# MCU.net
KiCad netlist of a schematic drawn in Altium Designer
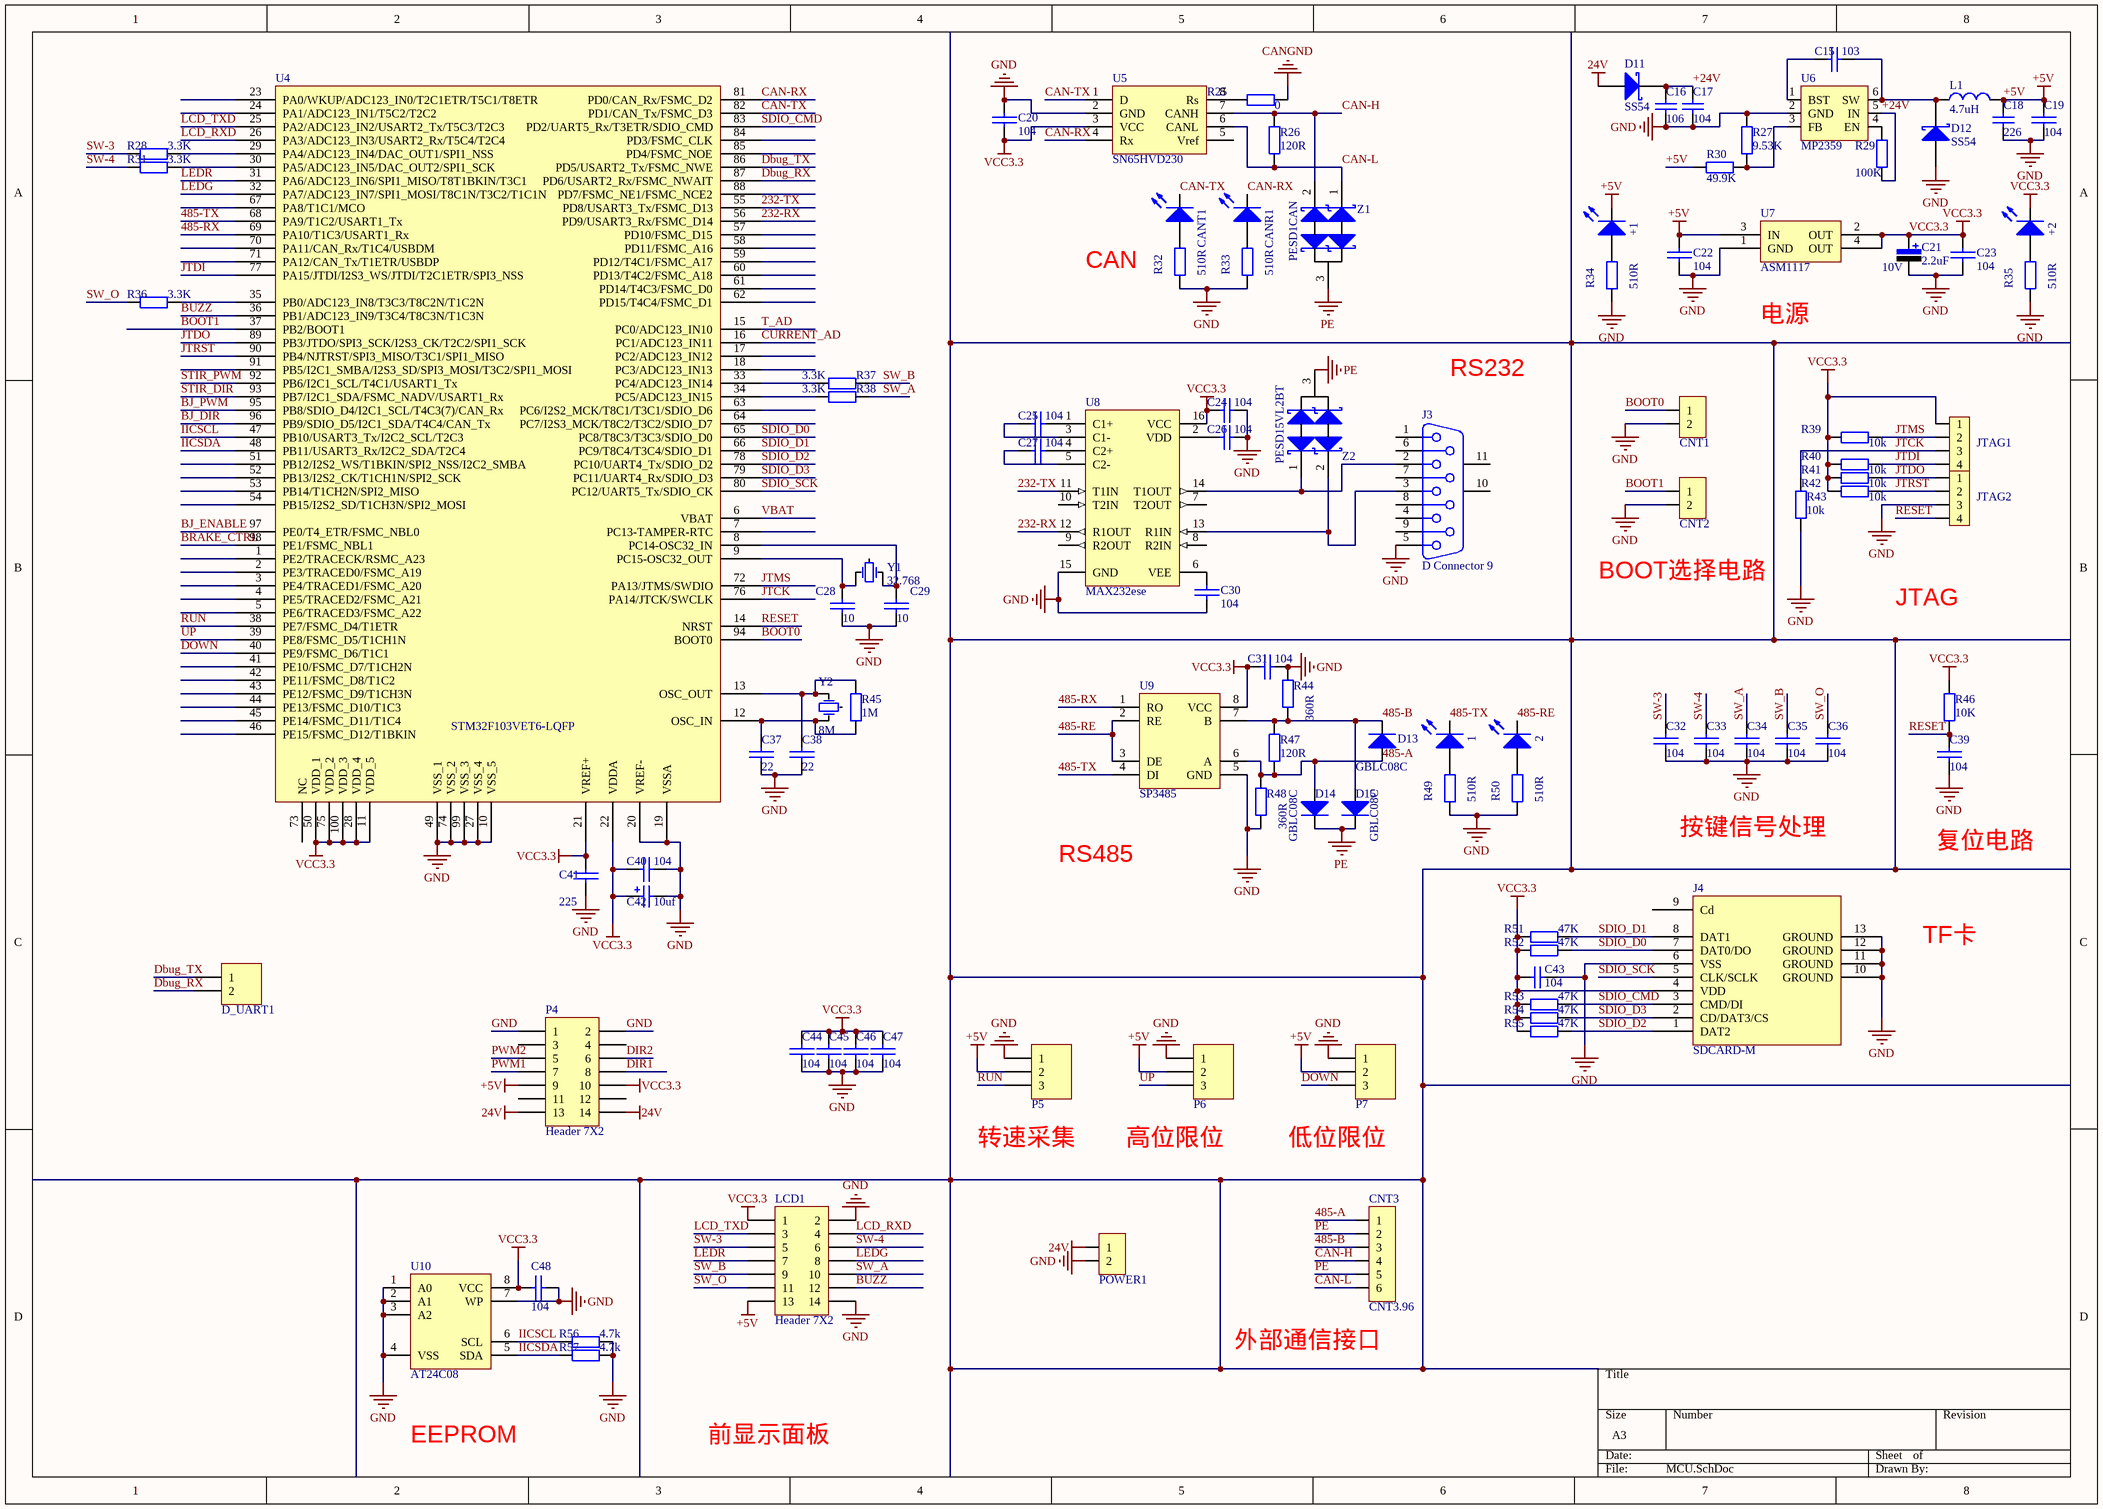
[diagram p0: MCU.SchDoc]

(export (version "E")
  (design (tool "Eeschema 10.0.6"))
  (components
    (comp (ref "+1") (value "COLOUR") (footprint "0603LED") (libsource (lib "MY_Library") (part "ledφ6")))
    (comp (ref "+2") (value "COLOUR") (footprint "0603LED") (libsource (lib "MY_Library") (part "ledφ6")))
    (comp (ref "1") (value "COLOUR") (footprint "0603LED") (libsource (lib "MY_Library") (part "ledφ6")))
    (comp (ref "2") (value "COLOUR") (footprint "0603LED") (libsource (lib "MY_Library") (part "ledφ6")))
    (comp (ref "C15")
      (value "103")
      (footprint "0603C")
      (description "安规电容")
      (libsource (lib "MY_Library") (part "CAP X"))
    )
    (comp (ref "C16")
      (value "1210")
      (footprint "1210")
      (description "无极性电容")
      (fields (field (name "容量") "106") (field (name "PUBLISHER") "Altium Limited"))
      (libsource (lib "altium-import") (part "root_1_Cap_"))
    )
    (comp (ref "C17")
      (value "104")
      (footprint "0603-2")
      (description "无极性电容")
      (fields (field (name "Comment") "Cap") (field (name "PUBLISHER") "Altium Limited"))
      (libsource (lib "Fszhang") (part "Cap"))
    )
    (comp (ref "C18")
      (value "226")
      (footprint "1206")
      (description "无极性电容")
      (fields (field (name "Comment") "Cap") (field (name "PUBLISHER") "Altium Limited"))
      (libsource (lib "Fszhang") (part "Cap"))
    )
    (comp (ref "C19")
      (value "104")
      (footprint "0603C")
      (description "安规电容")
      (libsource (lib "MY_Library") (part "CAP X"))
    )
    (comp (ref "C20")
      (value "104")
      (footprint "0603C")
      (description "安规电容")
      (libsource (lib "MY_Library") (part "CAP X"))
    )
    (comp (ref "C21")
      (value "2.2uF")
      (footprint "CAP-3216")
      (description "极性电解电容")
      (fields
        (field (name "VOL") "10V")
        (field (name "Comment") "Cap Pol")
        (field (name "PUBLISHER") "Altium Limited")
      )
      (libsource (lib "Fszhang") (part "Cap Pol"))
    )
    (comp (ref "C22")
      (value "104")
      (footprint "0603C")
      (description "安规电容")
      (libsource (lib "MY_Library") (part "CAP X"))
    )
    (comp (ref "C23")
      (value "104")
      (footprint "0603C")
      (description "安规电容")
      (libsource (lib "MY_Library") (part "CAP X"))
    )
    (comp (ref "C24")
      (value "104")
      (footprint "0603C")
      (description "安规电容")
      (libsource (lib "MY_Library") (part "CAP X"))
    )
    (comp (ref "C25")
      (value "104")
      (footprint "0603C")
      (description "安规电容")
      (libsource (lib "MY_Library") (part "CAP X"))
    )
    (comp (ref "C26")
      (value "104")
      (footprint "0603C")
      (description "安规电容")
      (libsource (lib "MY_Library") (part "CAP X"))
    )
    (comp (ref "C27")
      (value "104")
      (footprint "0603C")
      (description "安规电容")
      (libsource (lib "MY_Library") (part "CAP X"))
    )
    (comp (ref "C28")
      (value "10")
      (footprint "0603C")
      (description "安规电容")
      (libsource (lib "MY_Library") (part "CAP X"))
    )
    (comp (ref "C29")
      (value "10")
      (footprint "0603C")
      (description "安规电容")
      (libsource (lib "MY_Library") (part "CAP X"))
    )
    (comp (ref "C30")
      (value "104")
      (footprint "0603C")
      (description "安规电容")
      (libsource (lib "MY_Library") (part "CAP X"))
    )
    (comp (ref "C31")
      (value "104")
      (footprint "0603C")
      (description "安规电容")
      (libsource (lib "MY_Library") (part "CAP X"))
    )
    (comp (ref "C32")
      (value "104")
      (footprint "0603C")
      (description "安规电容")
      (libsource (lib "MY_Library") (part "CAP X"))
    )
    (comp (ref "C33")
      (value "104")
      (footprint "0603C")
      (description "安规电容")
      (libsource (lib "MY_Library") (part "CAP X"))
    )
    (comp (ref "C34")
      (value "104")
      (footprint "0603C")
      (description "安规电容")
      (libsource (lib "MY_Library") (part "CAP X"))
    )
    (comp (ref "C35")
      (value "104")
      (footprint "0603C")
      (description "安规电容")
      (libsource (lib "MY_Library") (part "CAP X"))
    )
    (comp (ref "C36")
      (value "104")
      (footprint "0603C")
      (description "安规电容")
      (libsource (lib "MY_Library") (part "CAP X"))
    )
    (comp (ref "C37")
      (value "22")
      (footprint "0603C")
      (description "安规电容")
      (libsource (lib "MY_Library") (part "CAP X"))
    )
    (comp (ref "C38")
      (value "22")
      (footprint "0603C")
      (description "安规电容")
      (libsource (lib "MY_Library") (part "CAP X"))
    )
    (comp (ref "C39")
      (value "104")
      (footprint "0603C")
      (description "安规电容")
      (libsource (lib "MY_Library") (part "CAP X"))
    )
    (comp (ref "C40")
      (value "104")
      (footprint "0603C")
      (description "安规电容")
      (libsource (lib "MY_Library") (part "CAP X"))
    )
    (comp (ref "C41")
      (value "225")
      (footprint "0603C")
      (description "安规电容")
      (libsource (lib "MY_Library") (part "CAP X"))
    )
    (comp (ref "C42")
      (value "10uf")
      (footprint "ct3216-18")
      (description "电解电容")
      (libsource (lib "MY_Library") (part "CAP"))
    )
    (comp (ref "C43")
      (value "104")
      (footprint "C-RAD-0603")
      (description "无极性电容")
      (fields (field (name "Comment") "Cap") (field (name "PUBLISHER") "Altium Limited"))
      (libsource (lib "Fszhang") (part "Cap"))
    )
    (comp (ref "C44")
      (value "104")
      (footprint "0603C")
      (description "安规电容")
      (libsource (lib "MY_Library") (part "CAP X"))
    )
    (comp (ref "C45")
      (value "104")
      (footprint "0603C")
      (description "安规电容")
      (libsource (lib "MY_Library") (part "CAP X"))
    )
    (comp (ref "C46")
      (value "104")
      (footprint "0603C")
      (description "安规电容")
      (libsource (lib "MY_Library") (part "CAP X"))
    )
    (comp (ref "C47")
      (value "104")
      (footprint "0603C")
      (description "安规电容")
      (libsource (lib "MY_Library") (part "CAP X"))
    )
    (comp (ref "C48")
      (value "104")
      (footprint "0603C")
      (description "安规电容")
      (libsource (lib "MY_Library") (part "CAP X"))
    )
    (comp (ref "CANR1") (value "COLOUR") (footprint "0603LED") (libsource (lib "MY_Library") (part "ledφ6")))
    (comp (ref "CANT1") (value "COLOUR") (footprint "0603LED") (libsource (lib "MY_Library") (part "ledφ6")))
    (comp (ref "CNT1") (value "cnt2p") (footprint "cont-1") (libsource (lib "MY_Library") (part "cnt2p")))
    (comp (ref "CNT2") (value "cnt2p") (footprint "cont-1") (libsource (lib "MY_Library") (part "cnt2p")))
    (comp (ref "CNT3")
      (value "CNT3.96")
      (footprint "CNT3.96")
      (description "接线端子(3.96MM)")
      (libsource (lib "MY_Library") (part "CNT3.96"))
    )
    (comp (ref "D11")
      (value "D-Schottky")
      (footprint "DIODE-SMA")
      (description "肖特基二极管")
      (fields (field (name "TYPE") "SS54") (field (name "PUBLISHER") "Altium Limited"))
      (libsource (lib "Fszhang") (part "D-Schottky"))
    )
    (comp (ref "D12")
      (value "D-Schottky")
      (footprint "DIODE-SMA")
      (description "肖特基二极管")
      (fields (field (name "TYPE") "SS54") (field (name "PUBLISHER") "Altium Limited"))
      (libsource (lib "Fszhang") (part "D-Schottky"))
    )
    (comp (ref "D13")
      (value "TVS")
      (footprint "DIODE-1206")
      (description "TVS保护")
      (fields (field (name "TYPE") "GBLC08C") (field (name "PUBLISHER") "Altium Limited"))
      (libsource (lib "Fszhang") (part "TVS"))
    )
    (comp (ref "D14")
      (value "TVS")
      (footprint "DIODE-1206")
      (description "TVS保护")
      (fields (field (name "TYPE") "GBLC08C") (field (name "PUBLISHER") "Altium Limited"))
      (libsource (lib "Fszhang") (part "TVS"))
    )
    (comp (ref "D15")
      (value "TVS")
      (footprint "DIODE-1206")
      (description "TVS保护")
      (fields (field (name "TYPE") "GBLC08C") (field (name "PUBLISHER") "Altium Limited"))
      (libsource (lib "Fszhang") (part "TVS"))
    )
    (comp (ref "D_UART1")
      (value "Header 2")
      (footprint "HDR2X1_A")
      (description "接插件")
      (fields (field (name "PUBLISHER") "Altium Limited"))
      (libsource (lib "Fszhang") (part "Header 2"))
    )
    (comp (ref "J3")
      (value "D Connector 9")
      (footprint "DB9-F")
      (description "串口")
      (fields (field (name "PUBLISHER") "Altium Limited"))
      (libsource (lib "Fszhang") (part "D Connector 9"))
    )
    (comp (ref "J4")
      (value "SDCARD-M")
      (footprint "SDCARD-M")
      (description "TF卡槽")
      (libsource (lib "Fszhang") (part "SDCARD-M"))
    )
    (comp (ref "JTAG1")
      (value "单排插针11mm4p")
      (footprint "单排插针2.54")
      (libsource (lib "MY_Library") (part "单排插针11mm4p"))
    )
    (comp (ref "JTAG2")
      (value "单排插针11mm4p")
      (footprint "单排插针2.54")
      (libsource (lib "MY_Library") (part "单排插针11mm4p"))
    )
    (comp (ref "L1")
      (value "4.7uH")
      (footprint "L-SMD-7")
      (description "电感")
      (fields (field (name "Comment") "Inductor") (field (name "PUBLISHER") "Altium Limited"))
      (libsource (lib "Fszhang") (part "Inductor"))
    )
    (comp (ref "LCD1")
      (value "Header 7X2")
      (footprint "HDR7X2_A1")
      (description "Header, 7-Pin")
      (fields (field (name "PUBLISHER") "Altium Limited"))
      (libsource (lib "Fszhang") (part "Header 7X2"))
    )
    (comp (ref "P4")
      (value "Header 7X2")
      (footprint "HDR7X2_A1")
      (description "Header, 7-Pin")
      (fields (field (name "PUBLISHER") "Altium Limited"))
      (libsource (lib "Fszhang") (part "Header 7X2"))
    )
    (comp (ref "P5")
      (value "Header 3")
      (footprint "XH2.54*3卧贴")
      (description "接插件")
      (fields (field (name "PUBLISHER") "Altium Limited"))
      (libsource (lib "Fszhang") (part "Header 3"))
    )
    (comp (ref "P6")
      (value "Header 3")
      (footprint "XH2.54*3卧贴")
      (description "接插件")
      (fields (field (name "PUBLISHER") "Altium Limited"))
      (libsource (lib "Fszhang") (part "Header 3"))
    )
    (comp (ref "P7")
      (value "Header 3")
      (footprint "XH2.54*3卧贴")
      (description "接插件")
      (fields (field (name "PUBLISHER") "Altium Limited"))
      (libsource (lib "Fszhang") (part "Header 3"))
    )
    (comp (ref "POWER1")
      (value "CNT5.08MM*2 WAN")
      (footprint "CNT5.08*2WAN")
      (libsource (lib "MY_Library") (part "CNT5.08MM*2 WAN"))
    )
    (comp (ref "R25")
      (value "0")
      (footprint "0603-1")
      (description "贴片电阻")
      (fields (field (name "Comment") "Res1") (field (name "PUBLISHER") "Altium Limited"))
      (libsource (lib "") (part "Res1_1"))
    )
    (comp (ref "R26")
      (value "120R")
      (footprint "0603-1")
      (description "贴片电阻")
      (fields (field (name "Comment") "Res1") (field (name "PUBLISHER") "Altium Limited"))
      (libsource (lib "Fszhang") (part "Res1"))
    )
    (comp (ref "R27")
      (value "9.53K")
      (footprint "0603-1")
      (description "贴片电阻")
      (fields (field (name "Comment") "Res1") (field (name "PUBLISHER") "Altium Limited"))
      (libsource (lib "Fszhang") (part "Res1"))
    )
    (comp (ref "R28")
      (value "3.3K")
      (footprint "0603-1")
      (description "贴片电阻")
      (fields (field (name "Comment") "Res1") (field (name "PUBLISHER") "Altium Limited"))
      (libsource (lib "") (part "Res1_1"))
    )
    (comp (ref "R29")
      (value "100K")
      (footprint "0603-1")
      (description "贴片电阻")
      (fields (field (name "Comment") "Res1") (field (name "PUBLISHER") "Altium Limited"))
      (libsource (lib "Fszhang") (part "Res1"))
    )
    (comp (ref "R30")
      (value "49.9K")
      (footprint "0603-1")
      (description "贴片电阻")
      (fields (field (name "Comment") "Res1") (field (name "PUBLISHER") "Altium Limited"))
      (libsource (lib "") (part "Res1_1"))
    )
    (comp (ref "R31")
      (value "3.3K")
      (footprint "0603-1")
      (description "贴片电阻")
      (fields (field (name "Comment") "Res1") (field (name "PUBLISHER") "Altium Limited"))
      (libsource (lib "") (part "Res1_1"))
    )
    (comp (ref "R32")
      (value "510R")
      (footprint "0603-1")
      (description "贴片电阻")
      (fields (field (name "Comment") "Res1") (field (name "PUBLISHER") "Altium Limited"))
      (libsource (lib "Fszhang") (part "Res1"))
    )
    (comp (ref "R33")
      (value "510R")
      (footprint "0603-1")
      (description "贴片电阻")
      (fields (field (name "Comment") "Res1") (field (name "PUBLISHER") "Altium Limited"))
      (libsource (lib "Fszhang") (part "Res1"))
    )
    (comp (ref "R34")
      (value "510R")
      (footprint "0603-1")
      (description "贴片电阻")
      (fields (field (name "Comment") "Res1") (field (name "PUBLISHER") "Altium Limited"))
      (libsource (lib "Fszhang") (part "Res1"))
    )
    (comp (ref "R35")
      (value "510R")
      (footprint "0603-1")
      (description "贴片电阻")
      (fields (field (name "Comment") "Res1") (field (name "PUBLISHER") "Altium Limited"))
      (libsource (lib "Fszhang") (part "Res1"))
    )
    (comp (ref "R36")
      (value "3.3K")
      (footprint "0603-1")
      (description "贴片电阻")
      (fields (field (name "Comment") "Res1") (field (name "PUBLISHER") "Altium Limited"))
      (libsource (lib "") (part "Res1_1"))
    )
    (comp (ref "R37")
      (value "3.3K")
      (footprint "0603-1")
      (description "贴片电阻")
      (fields (field (name "Comment") "Res1") (field (name "PUBLISHER") "Altium Limited"))
      (libsource (lib "") (part "Res1_2"))
    )
    (comp (ref "R38")
      (value "3.3K")
      (footprint "0603-1")
      (description "贴片电阻")
      (fields (field (name "Comment") "Res1") (field (name "PUBLISHER") "Altium Limited"))
      (libsource (lib "") (part "Res1_2"))
    )
    (comp (ref "R39")
      (value "10k")
      (footprint "0603-1")
      (description "贴片电阻")
      (fields (field (name "Comment") "Res1") (field (name "PUBLISHER") "Altium Limited"))
      (libsource (lib "") (part "Res1_1"))
    )
    (comp (ref "R40")
      (value "10k")
      (footprint "0603-1")
      (description "贴片电阻")
      (fields (field (name "Comment") "Res1") (field (name "PUBLISHER") "Altium Limited"))
      (libsource (lib "") (part "Res1_1"))
    )
    (comp (ref "R41")
      (value "10k")
      (footprint "0603-1")
      (description "贴片电阻")
      (fields (field (name "Comment") "Res1") (field (name "PUBLISHER") "Altium Limited"))
      (libsource (lib "") (part "Res1_1"))
    )
    (comp (ref "R42")
      (value "10k")
      (footprint "0603-1")
      (description "贴片电阻")
      (fields (field (name "Comment") "Res1") (field (name "PUBLISHER") "Altium Limited"))
      (libsource (lib "") (part "Res1_1"))
    )
    (comp (ref "R43")
      (value "10k")
      (footprint "0603-1")
      (description "贴片电阻")
      (fields (field (name "Comment") "Res1") (field (name "PUBLISHER") "Altium Limited"))
      (libsource (lib "") (part "Res1_3"))
    )
    (comp (ref "R44")
      (value "360R")
      (footprint "0603-1")
      (description "贴片电阻")
      (fields (field (name "Comment") "Res1") (field (name "PUBLISHER") "Altium Limited"))
      (libsource (lib "Fszhang") (part "Res1"))
    )
    (comp (ref "R45")
      (value "1M")
      (footprint "0603-1")
      (description "贴片电阻")
      (fields (field (name "Comment") "Res1") (field (name "PUBLISHER") "Altium Limited"))
      (libsource (lib "Fszhang") (part "Res1"))
    )
    (comp (ref "R46")
      (value "10K")
      (footprint "0603-1")
      (description "贴片电阻")
      (fields (field (name "Comment") "Res1") (field (name "PUBLISHER") "Altium Limited"))
      (libsource (lib "Fszhang") (part "Res1"))
    )
    (comp (ref "R47")
      (value "120R")
      (footprint "0603-1")
      (description "贴片电阻")
      (fields (field (name "Comment") "Res1") (field (name "PUBLISHER") "Altium Limited"))
      (libsource (lib "Fszhang") (part "Res1"))
    )
    (comp (ref "R48")
      (value "360R")
      (footprint "0603-1")
      (description "贴片电阻")
      (fields (field (name "Comment") "Res1") (field (name "PUBLISHER") "Altium Limited"))
      (libsource (lib "Fszhang") (part "Res1"))
    )
    (comp (ref "R49")
      (value "510R")
      (footprint "0603-1")
      (description "贴片电阻")
      (fields (field (name "Comment") "Res1") (field (name "PUBLISHER") "Altium Limited"))
      (libsource (lib "Fszhang") (part "Res1"))
    )
    (comp (ref "R50")
      (value "510R")
      (footprint "0603-1")
      (description "贴片电阻")
      (fields (field (name "Comment") "Res1") (field (name "PUBLISHER") "Altium Limited"))
      (libsource (lib "Fszhang") (part "Res1"))
    )
    (comp (ref "R51")
      (value "47K")
      (footprint "0603-1")
      (description "贴片电阻")
      (fields (field (name "Comment") "Res1") (field (name "PUBLISHER") "Altium Limited"))
      (libsource (lib "") (part "Res1_2"))
    )
    (comp (ref "R52")
      (value "47K")
      (footprint "0603-1")
      (description "贴片电阻")
      (fields (field (name "Comment") "Res1") (field (name "PUBLISHER") "Altium Limited"))
      (libsource (lib "") (part "Res1_2"))
    )
    (comp (ref "R53")
      (value "47K")
      (footprint "0603-1")
      (description "贴片电阻")
      (fields (field (name "Comment") "Res1") (field (name "PUBLISHER") "Altium Limited"))
      (libsource (lib "") (part "Res1_2"))
    )
    (comp (ref "R54")
      (value "47K")
      (footprint "0603-1")
      (description "贴片电阻")
      (fields (field (name "Comment") "Res1") (field (name "PUBLISHER") "Altium Limited"))
      (libsource (lib "") (part "Res1_2"))
    )
    (comp (ref "R55")
      (value "47K")
      (footprint "0603-1")
      (description "贴片电阻")
      (fields (field (name "Comment") "Res1") (field (name "PUBLISHER") "Altium Limited"))
      (libsource (lib "") (part "Res1_2"))
    )
    (comp (ref "R56")
      (value "4.7k")
      (footprint "0603-1")
      (description "贴片电阻")
      (fields (field (name "Comment") "Res1") (field (name "PUBLISHER") "Altium Limited"))
      (libsource (lib "") (part "Res1_1"))
    )
    (comp (ref "R57")
      (value "4.7k")
      (footprint "0603-1")
      (description "贴片电阻")
      (fields (field (name "Comment") "Res1") (field (name "PUBLISHER") "Altium Limited"))
      (libsource (lib "") (part "Res1_1"))
    )
    (comp (ref "U4")
      (value "STM32F103VET6-LQFP")
      (footprint "LQFP-100_M")
      (description "STM32单片机100引脚")
      (libsource (lib "Fszhang") (part "STM32F103V"))
    )
    (comp (ref "U5")
      (value "SN65HVD230")
      (footprint "NSO8_N")
      (description "CAN芯片")
      (libsource (lib "Fszhang") (part "SN65HVD230"))
    )
    (comp (ref "U6")
      (value "MP2359")
      (footprint "SOT23-6")
      (description "DC降压24V 1.2A")
      (libsource (lib "Fszhang") (part "MP2359"))
    )
    (comp (ref "U7")
      (value "ASM1117")
      (footprint "SOT-223")
      (description "3.3V稳压芯片")
      (libsource (lib "Fszhang") (part "ASM1117"))
    )
    (comp (ref "U8")
      (value "MAX232ese")
      (footprint "NSO16_M")
      (description "+5V Powered, Multi-Channel RS-232 Driver/Receiver")
      (fields (field (name "PUBLISHER") "Altium Limited"))
      (libsource (lib "Fszhang") (part "MAX232"))
    )
    (comp (ref "U9")
      (value "SP3485")
      (footprint "NSO8_N")
      (description "485总线芯片")
      (libsource (lib "Fszhang") (part "SP3485"))
    )
    (comp (ref "U10")
      (value "AT24C08")
      (footprint "SOIC8_N")
      (description "EEROM存储器")
      (libsource (lib "Fszhang") (part "AT24C02"))
    )
    (comp (ref "Y1")
      (value "32.768")
      (footprint "MC-146")
      (description "圆柱晶振")
      (fields (field (name "Comment") "XTAL_SM") (field (name "PUBLISHER") "Altium Limited"))
      (libsource (lib "Fszhang") (part "XTAL_SM"))
    )
    (comp (ref "Y2")
      (value "8M")
      (footprint "xtal3225")
      (description "圆柱晶振")
      (fields (field (name "Comment") "XTAL_SM") (field (name "PUBLISHER") "Altium Limited"))
      (libsource (lib "Fszhang") (part "XTAL_SM"))
    )
    (comp (ref "Z1")
      (value "PESD1CAN")
      (footprint "SOT-23")
      (description "过压保护")
      (libsource (lib "Fszhang") (part "PESD1CAN"))
    )
    (comp (ref "Z2")
      (value "PESD15VL2BT")
      (footprint "SOT-23")
      (description "过压保护")
      (libsource (lib "Fszhang") (part "PESD1CAN"))
    )
  )
  (nets
    (net (code "1") (name "+5V") (class "Default")
      (node (ref "+1") (pin "2") (pinfunction "-_2") (pintype "passive"))
      (node (ref "C18") (pin "2") (pinfunction "2_2") (pintype "passive"))
      (node (ref "C19") (pin "1") (pinfunction "1_1") (pintype "passive"))
      (node (ref "C22") (pin "1") (pinfunction "1_1") (pintype "passive"))
      (node (ref "L1") (pin "2") (pinfunction "2_2") (pintype "passive"))
      (node (ref "LCD1") (pin "13") (pinfunction "13_13") (pintype "passive"))
      (node (ref "P4") (pin "9") (pinfunction "9_9") (pintype "passive"))
      (node (ref "P5") (pin "2") (pinfunction "2_2") (pintype "passive"))
      (node (ref "P6") (pin "2") (pinfunction "2_2") (pintype "passive"))
      (node (ref "P7") (pin "2") (pinfunction "2_2") (pintype "passive"))
      (node (ref "R30") (pin "2") (pinfunction "2_2") (pintype "passive"))
      (node (ref "U7") (pin "3") (pinfunction "IN_3") (pintype "passive"))
    )
    (net (code "2") (name "/+24V") (class "Default")
      (node (ref "C16") (pin "2") (pinfunction "2_2") (pintype "passive"))
      (node (ref "C17") (pin "2") (pinfunction "2_2") (pintype "passive"))
      (node (ref "D11") (pin "2") (pinfunction "K_2") (pintype "passive"))
      (node (ref "R29") (pin "1") (pinfunction "1_1") (pintype "passive"))
      (node (ref "U6") (pin "5") (pinfunction "IN_5") (pintype "passive"))
    )
    (net (code "3") (name "/232-RX") (class "Default")
      (node (ref "U4") (pin "56") (pinfunction "PD9/USART3_Rx/FSMC_D14_56") (pintype "passive"))
      (node (ref "U8") (pin "12") (pinfunction "R1OUT_12") (pintype "output"))
    )
    (net (code "4") (name "/232-TX") (class "Default")
      (node (ref "U4") (pin "55") (pinfunction "PD8/USART3_Tx/FSMC_D13_55") (pintype "passive"))
      (node (ref "U8") (pin "11") (pinfunction "T1IN_11") (pintype "input"))
    )
    (net (code "5") (name "/485-A") (class "Default")
      (node (ref "CNT3") (pin "1") (pinfunction "1_1") (pintype "passive"))
      (node (ref "D13") (pin "1") (pinfunction "A_1") (pintype "passive"))
      (node (ref "D14") (pin "1") (pinfunction "A_1") (pintype "passive"))
      (node (ref "R47") (pin "1") (pinfunction "1_1") (pintype "passive"))
      (node (ref "R48") (pin "2") (pinfunction "2_2") (pintype "passive"))
      (node (ref "U9") (pin "6") (pinfunction "A_6") (pintype "passive"))
    )
    (net (code "6") (name "/485-B") (class "Default")
      (node (ref "CNT3") (pin "3") (pinfunction "3_3") (pintype "passive"))
      (node (ref "D13") (pin "2") (pinfunction "K_2") (pintype "passive"))
      (node (ref "D15") (pin "1") (pinfunction "A_1") (pintype "passive"))
      (node (ref "R44") (pin "1") (pinfunction "1_1") (pintype "passive"))
      (node (ref "R47") (pin "2") (pinfunction "2_2") (pintype "passive"))
      (node (ref "U9") (pin "7") (pinfunction "B_7") (pintype "passive"))
    )
    (net (code "7") (name "/485-RE") (class "Default")
      (node (ref "2") (pin "2") (pinfunction "-_2") (pintype "passive"))
      (node (ref "U9") (pin "2") (pinfunction "RE_2") (pintype "passive"))
      (node (ref "U9") (pin "3") (pinfunction "DE_3") (pintype "passive"))
    )
    (net (code "8") (name "/485-RX") (class "Default")
      (node (ref "U4") (pin "69") (pinfunction "PA10/T1C3/USART1_Rx_69") (pintype "passive"))
      (node (ref "U9") (pin "1") (pinfunction "RO_1") (pintype "passive"))
    )
    (net (code "9") (name "/485-TX") (class "Default")
      (node (ref "1") (pin "2") (pinfunction "-_2") (pintype "passive"))
      (node (ref "U4") (pin "68") (pinfunction "PA9/T1C2/USART1_Tx_68") (pintype "passive"))
      (node (ref "U9") (pin "4") (pinfunction "DI_4") (pintype "passive"))
    )
    (net (code "10") (name "/BJ_DIR") (class "Default")
      (node (ref "U4") (pin "96") (pinfunction "PB9/SDIO_D5/I2C1_SDA/T4C4/CAN_Tx_96") (pintype "passive"))
    )
    (net (code "11") (name "/BJ_ENABLE") (class "Default")
      (node (ref "U4") (pin "97") (pinfunction "PE0/T4_ETR/FSMC_NBL0_97") (pintype "passive"))
    )
    (net (code "12") (name "/BJ_PWM") (class "Default")
      (node (ref "U4") (pin "95") (pinfunction "PB8/SDIO_D4/I2C1_SCL/T4C3(7)/CAN_Rx_95") (pintype "passive"))
    )
    (net (code "13") (name "/BOOT0") (class "Default")
      (node (ref "CNT1") (pin "1") (pinfunction "1_1") (pintype "passive"))
      (node (ref "U4") (pin "94") (pinfunction "BOOT0_94") (pintype "passive"))
    )
    (net (code "14") (name "/BOOT1") (class "Default")
      (node (ref "CNT2") (pin "1") (pinfunction "1_1") (pintype "passive"))
      (node (ref "U4") (pin "37") (pinfunction "PB2/BOOT1_37") (pintype "passive"))
    )
    (net (code "15") (name "/BRAKE_CTRL") (class "Default")
      (node (ref "U4") (pin "98") (pinfunction "PE1/FSMC_NBL1_98") (pintype "passive"))
    )
    (net (code "16") (name "/BUZZ") (class "Default")
      (node (ref "LCD1") (pin "12") (pinfunction "12_12") (pintype "passive"))
      (node (ref "U4") (pin "36") (pinfunction "PB1/ADC123_IN9/T3C4/T8C3N/T1C3N_36") (pintype "passive"))
    )
    (net (code "17") (name "/CAN-H") (class "Default")
      (node (ref "CNT3") (pin "4") (pinfunction "4_4") (pintype "passive"))
      (node (ref "R26") (pin "2") (pinfunction "2_2") (pintype "passive"))
      (node (ref "U5") (pin "7") (pinfunction "CANH_7") (pintype "passive"))
      (node (ref "Z1") (pin "2") (pintype "passive"))
    )
    (net (code "18") (name "/CAN-L") (class "Default")
      (node (ref "CNT3") (pin "6") (pinfunction "6_6") (pintype "passive"))
      (node (ref "R26") (pin "1") (pinfunction "1_1") (pintype "passive"))
      (node (ref "U5") (pin "6") (pinfunction "CANL_6") (pintype "passive"))
      (node (ref "Z1") (pin "1") (pintype "passive"))
    )
    (net (code "19") (name "/CAN-RX") (class "Default")
      (node (ref "CANR1") (pin "2") (pinfunction "-_2") (pintype "passive"))
      (node (ref "U4") (pin "81") (pinfunction "PD0/CAN_Rx/FSMC_D2_81") (pintype "passive"))
      (node (ref "U5") (pin "4") (pinfunction "Rx_4") (pintype "passive"))
    )
    (net (code "20") (name "/CAN-TX") (class "Default")
      (node (ref "CANT1") (pin "2") (pinfunction "-_2") (pintype "passive"))
      (node (ref "U4") (pin "82") (pinfunction "PD1/CAN_Tx/FSMC_D3_82") (pintype "passive"))
      (node (ref "U5") (pin "1") (pinfunction "D_1") (pintype "passive"))
    )
    (net (code "21") (name "/CURRENT_AD") (class "Default")
      (node (ref "U4") (pin "16") (pinfunction "PC1/ADC123_IN11_16") (pintype "passive"))
    )
    (net (code "22") (name "/DIR1") (class "Default")
      (node (ref "P4") (pin "8") (pinfunction "8_8") (pintype "passive"))
    )
    (net (code "23") (name "/DIR2") (class "Default")
      (node (ref "P4") (pin "6") (pinfunction "6_6") (pintype "passive"))
    )
    (net (code "24") (name "/DOWN") (class "Default")
      (node (ref "P7") (pin "3") (pinfunction "3_3") (pintype "passive"))
      (node (ref "U4") (pin "40") (pinfunction "PE9/FSMC_D6/T1C1_40") (pintype "passive"))
    )
    (net (code "25") (name "/Dbug_RX") (class "Default")
      (node (ref "D_UART1") (pin "2") (pinfunction "2_2") (pintype "passive"))
      (node (ref "U4") (pin "87") (pinfunction "PD6/USART2_Rx/FSMC_NWAIT_87") (pintype "passive"))
    )
    (net (code "26") (name "/Dbug_TX") (class "Default")
      (node (ref "D_UART1") (pin "1") (pinfunction "1_1") (pintype "passive"))
      (node (ref "U4") (pin "86") (pinfunction "PD5/USART2_Tx/FSMC_NWE_86") (pintype "passive"))
    )
    (net (code "27") (name "/IICSCL") (class "Default")
      (node (ref "R56") (pin "2") (pinfunction "2_2") (pintype "passive"))
      (node (ref "U10") (pin "6") (pinfunction "SCL_6") (pintype "passive"))
      (node (ref "U4") (pin "47") (pinfunction "PB10/USART3_Tx/I2C2_SCL/T2C3_47") (pintype "passive"))
    )
    (net (code "28") (name "/IICSDA") (class "Default")
      (node (ref "R57") (pin "2") (pinfunction "2_2") (pintype "passive"))
      (node (ref "U10") (pin "5") (pinfunction "SDA_5") (pintype "passive"))
      (node (ref "U4") (pin "48") (pinfunction "PB11/USART3_Rx/I2C2_SDA/T2C4_48") (pintype "passive"))
    )
    (net (code "29") (name "/JTCK") (class "Default")
      (node (ref "JTAG1") (pin "3") (pinfunction "3_3") (pintype "passive"))
      (node (ref "R43") (pin "1") (pinfunction "1_1") (pintype "passive"))
      (node (ref "U4") (pin "76") (pinfunction "PA14/JTCK/SWCLK_76") (pintype "passive"))
    )
    (net (code "30") (name "/JTDI") (class "Default")
      (node (ref "JTAG1") (pin "4") (pinfunction "4_4") (pintype "passive"))
      (node (ref "R40") (pin "1") (pinfunction "1_1") (pintype "passive"))
      (node (ref "U4") (pin "77") (pinfunction "PA15/JTDI/I2S3_WS/JTDI/T2C1ETR/SPI3_NSS_77") (pintype "passive"))
    )
    (net (code "31") (name "/JTDO") (class "Default")
      (node (ref "JTAG2") (pin "1") (pinfunction "1_1") (pintype "passive"))
      (node (ref "R41") (pin "1") (pinfunction "1_1") (pintype "passive"))
      (node (ref "U4") (pin "89") (pinfunction "PB3/JTDO/SPI3_SCK/I2S3_CK/T2C2/SPI1_SCK_89") (pintype "passive"))
    )
    (net (code "32") (name "/JTMS") (class "Default")
      (node (ref "JTAG1") (pin "2") (pinfunction "2_2") (pintype "passive"))
      (node (ref "R39") (pin "1") (pinfunction "1_1") (pintype "passive"))
      (node (ref "U4") (pin "72") (pinfunction "PA13/JTMS/SWDIO_72") (pintype "passive"))
    )
    (net (code "33") (name "/JTRST") (class "Default")
      (node (ref "JTAG2") (pin "2") (pinfunction "2_2") (pintype "passive"))
      (node (ref "R42") (pin "1") (pinfunction "1_1") (pintype "passive"))
      (node (ref "U4") (pin "90") (pinfunction "PB4/NJTRST/SPI3_MISO/T3C1/SPI1_MISO_90") (pintype "passive"))
    )
    (net (code "34") (name "/LCD_RXD") (class "Default")
      (node (ref "LCD1") (pin "4") (pinfunction "4_4") (pintype "passive"))
      (node (ref "U4") (pin "26") (pinfunction "PA3/ADC123_IN3/USART2_Rx/T5C4/T2C4_26") (pintype "passive"))
    )
    (net (code "35") (name "/LCD_TXD") (class "Default")
      (node (ref "LCD1") (pin "3") (pinfunction "3_3") (pintype "passive"))
      (node (ref "U4") (pin "25") (pinfunction "PA2/ADC123_IN2/USART2_Tx/T5C3/T2C3_25") (pintype "passive"))
    )
    (net (code "36") (name "/LEDG") (class "Default")
      (node (ref "LCD1") (pin "8") (pinfunction "8_8") (pintype "passive"))
      (node (ref "U4") (pin "32") (pinfunction "PA7/ADC123_IN7/SPI1_MOSI/T8C1N/T3C2/T1C1N_32") (pintype "passive"))
    )
    (net (code "37") (name "/LEDR") (class "Default")
      (node (ref "LCD1") (pin "7") (pinfunction "7_7") (pintype "passive"))
      (node (ref "U4") (pin "31") (pinfunction "PA6/ADC123_IN6/SPI1_MISO/T8T1BKIN/T3C1_31") (pintype "passive"))
    )
    (net (code "38") (name "/PWM1") (class "Default")
      (node (ref "P4") (pin "7") (pinfunction "7_7") (pintype "passive"))
    )
    (net (code "39") (name "/PWM2") (class "Default")
      (node (ref "P4") (pin "5") (pinfunction "5_5") (pintype "passive"))
    )
    (net (code "40") (name "/RESET") (class "Default")
      (node (ref "C39") (pin "2") (pinfunction "2_2") (pintype "passive"))
      (node (ref "JTAG2") (pin "4") (pinfunction "4_4") (pintype "passive"))
      (node (ref "R46") (pin "1") (pinfunction "1_1") (pintype "passive"))
      (node (ref "U4") (pin "14") (pinfunction "NRST_14") (pintype "passive"))
    )
    (net (code "41") (name "/RUN") (class "Default")
      (node (ref "P5") (pin "3") (pinfunction "3_3") (pintype "passive"))
      (node (ref "U4") (pin "38") (pinfunction "PE7/FSMC_D4/T1ETR_38") (pintype "passive"))
    )
    (net (code "42") (name "/SDIO_CMD") (class "Default")
      (node (ref "J4") (pin "3") (pinfunction "CMD/DI_3") (pintype "passive"))
      (node (ref "R53") (pin "2") (pinfunction "2_2") (pintype "passive"))
      (node (ref "U4") (pin "83") (pinfunction "PD2/UART5_Rx/T3ETR/SDIO_CMD_83") (pintype "passive"))
    )
    (net (code "43") (name "/SDIO_D0") (class "Default")
      (node (ref "J4") (pin "7") (pinfunction "DAT0/DO_7") (pintype "passive"))
      (node (ref "R52") (pin "2") (pinfunction "2_2") (pintype "passive"))
      (node (ref "U4") (pin "65") (pinfunction "PC8/T8C3/T3C3/SDIO_D0_65") (pintype "passive"))
    )
    (net (code "44") (name "/SDIO_D1") (class "Default")
      (node (ref "J4") (pin "8") (pinfunction "DAT1_8") (pintype "passive"))
      (node (ref "R51") (pin "2") (pinfunction "2_2") (pintype "passive"))
      (node (ref "U4") (pin "66") (pinfunction "PC9/T8C4/T3C4/SDIO_D1_66") (pintype "passive"))
    )
    (net (code "45") (name "/SDIO_D2") (class "Default")
      (node (ref "J4") (pin "1") (pinfunction "DAT2_1") (pintype "passive"))
      (node (ref "R55") (pin "2") (pinfunction "2_2") (pintype "passive"))
      (node (ref "U4") (pin "78") (pinfunction "PC10/UART4_Tx/SDIO_D2_78") (pintype "passive"))
    )
    (net (code "46") (name "/SDIO_D3") (class "Default")
      (node (ref "J4") (pin "2") (pinfunction "CD/DAT3/CS_2") (pintype "passive"))
      (node (ref "R54") (pin "2") (pinfunction "2_2") (pintype "passive"))
      (node (ref "U4") (pin "79") (pinfunction "PC11/UART4_Rx/SDIO_D3_79") (pintype "passive"))
    )
    (net (code "47") (name "/SDIO_SCK") (class "Default")
      (node (ref "J4") (pin "5") (pinfunction "CLK/SCLK_5") (pintype "passive"))
      (node (ref "U4") (pin "80") (pinfunction "PC12/UART5_Tx/SDIO_CK_80") (pintype "passive"))
    )
    (net (code "48") (name "/STIR_DIR") (class "Default")
      (node (ref "U4") (pin "93") (pinfunction "PB7/I2C1_SDA/FSMC_NADV/USART1_Rx_93") (pintype "passive"))
    )
    (net (code "49") (name "/STIR_PWM") (class "Default")
      (node (ref "U4") (pin "92") (pinfunction "PB6/I2C1_SCL/T4C1/USART1_Tx_92") (pintype "passive"))
    )
    (net (code "50") (name "/SW-3") (class "Default")
      (node (ref "C32") (pin "1") (pinfunction "1_1") (pintype "passive"))
      (node (ref "LCD1") (pin "5") (pinfunction "5_5") (pintype "passive"))
      (node (ref "R28") (pin "2") (pinfunction "2_2") (pintype "passive"))
    )
    (net (code "51") (name "/SW-4") (class "Default")
      (node (ref "C33") (pin "1") (pinfunction "1_1") (pintype "passive"))
      (node (ref "LCD1") (pin "6") (pinfunction "6_6") (pintype "passive"))
      (node (ref "R31") (pin "2") (pinfunction "2_2") (pintype "passive"))
    )
    (net (code "52") (name "/SW_A") (class "Default")
      (node (ref "C34") (pin "1") (pinfunction "1_1") (pintype "passive"))
      (node (ref "LCD1") (pin "10") (pinfunction "10_10") (pintype "passive"))
      (node (ref "R38") (pin "2") (pinfunction "2_2") (pintype "passive"))
    )
    (net (code "53") (name "/SW_B") (class "Default")
      (node (ref "C35") (pin "1") (pinfunction "1_1") (pintype "passive"))
      (node (ref "LCD1") (pin "9") (pinfunction "9_9") (pintype "passive"))
      (node (ref "R37") (pin "2") (pinfunction "2_2") (pintype "passive"))
    )
    (net (code "54") (name "/SW_O") (class "Default")
      (node (ref "C36") (pin "1") (pinfunction "1_1") (pintype "passive"))
      (node (ref "LCD1") (pin "11") (pinfunction "11_11") (pintype "passive"))
      (node (ref "R36") (pin "2") (pinfunction "2_2") (pintype "passive"))
    )
    (net (code "55") (name "/T_AD") (class "Default")
      (node (ref "U4") (pin "15") (pinfunction "PC0/ADC123_IN10_15") (pintype "passive"))
    )
    (net (code "56") (name "/UP") (class "Default")
      (node (ref "P6") (pin "3") (pinfunction "3_3") (pintype "passive"))
      (node (ref "U4") (pin "39") (pinfunction "PE8/FSMC_D5/T1CH1N_39") (pintype "passive"))
    )
    (net (code "57") (name "/VBAT") (class "Default")
      (node (ref "U4") (pin "6") (pinfunction "VBAT_6") (pintype "passive"))
    )
    (net (code "58") (name "24V") (class "Default")
      (node (ref "D11") (pin "1") (pinfunction "A_1") (pintype "passive"))
      (node (ref "P4") (pin "13") (pinfunction "13_13") (pintype "passive"))
      (node (ref "P4") (pin "14") (pinfunction "14_14") (pintype "passive"))
      (node (ref "POWER1") (pin "1") (pinfunction "1_1") (pintype "passive"))
    )
    (net (code "59") (name "CANGND") (class "Default")
      (node (ref "R25") (pin "1") (pinfunction "1_1") (pintype "passive"))
    )
    (net (code "60") (name "GND") (class "Default")
      (node (ref "C16") (pin "1") (pinfunction "1_1") (pintype "passive"))
      (node (ref "C17") (pin "1") (pinfunction "1_1") (pintype "passive"))
      (node (ref "C18") (pin "1") (pinfunction "1_1") (pintype "passive"))
      (node (ref "C19") (pin "2") (pinfunction "2_2") (pintype "passive"))
      (node (ref "C20") (pin "1") (pinfunction "1_1") (pintype "passive"))
      (node (ref "C21") (pin "2") (pinfunction "2_2") (pintype "passive"))
      (node (ref "C22") (pin "2") (pinfunction "2_2") (pintype "passive"))
      (node (ref "C23") (pin "2") (pinfunction "2_2") (pintype "passive"))
      (node (ref "C24") (pin "1") (pinfunction "1_1") (pintype "passive"))
      (node (ref "C26") (pin "1") (pinfunction "1_1") (pintype "passive"))
      (node (ref "C28") (pin "2") (pinfunction "2_2") (pintype "passive"))
      (node (ref "C29") (pin "2") (pinfunction "2_2") (pintype "passive"))
      (node (ref "C30") (pin "1") (pinfunction "1_1") (pintype "passive"))
      (node (ref "C31") (pin "1") (pinfunction "1_1") (pintype "passive"))
      (node (ref "C32") (pin "2") (pinfunction "2_2") (pintype "passive"))
      (node (ref "C33") (pin "2") (pinfunction "2_2") (pintype "passive"))
      (node (ref "C34") (pin "2") (pinfunction "2_2") (pintype "passive"))
      (node (ref "C35") (pin "2") (pinfunction "2_2") (pintype "passive"))
      (node (ref "C36") (pin "2") (pinfunction "2_2") (pintype "passive"))
      (node (ref "C37") (pin "2") (pinfunction "2_2") (pintype "passive"))
      (node (ref "C38") (pin "2") (pinfunction "2_2") (pintype "passive"))
      (node (ref "C39") (pin "1") (pinfunction "1_1") (pintype "passive"))
      (node (ref "C40") (pin "1") (pinfunction "1_1") (pintype "passive"))
      (node (ref "C41") (pin "1") (pinfunction "1_1") (pintype "passive"))
      (node (ref "C42") (pin "2") (pinfunction "2_2") (pintype "passive"))
      (node (ref "C43") (pin "2") (pinfunction "2_2") (pintype "passive"))
      (node (ref "C44") (pin "1") (pinfunction "1_1") (pintype "passive"))
      (node (ref "C45") (pin "1") (pinfunction "1_1") (pintype "passive"))
      (node (ref "C46") (pin "1") (pinfunction "1_1") (pintype "passive"))
      (node (ref "C47") (pin "1") (pinfunction "1_1") (pintype "passive"))
      (node (ref "C48") (pin "1") (pinfunction "1_1") (pintype "passive"))
      (node (ref "CNT1") (pin "2") (pinfunction "2_2") (pintype "passive"))
      (node (ref "CNT2") (pin "2") (pinfunction "2_2") (pintype "passive"))
      (node (ref "D12") (pin "1") (pinfunction "A_1") (pintype "passive"))
      (node (ref "J3") (pin "5") (pinfunction "5_5") (pintype "passive"))
      (node (ref "J4") (pin "10") (pinfunction "GROUND_10") (pintype "passive"))
      (node (ref "J4") (pin "11") (pinfunction "GROUND_11") (pintype "passive"))
      (node (ref "J4") (pin "12") (pinfunction "GROUND_12") (pintype "passive"))
      (node (ref "J4") (pin "13") (pinfunction "GROUND_13") (pintype "passive"))
      (node (ref "J4") (pin "6") (pinfunction "VSS_6") (pintype "passive"))
      (node (ref "JTAG2") (pin "3") (pinfunction "3_3") (pintype "passive"))
      (node (ref "LCD1") (pin "14") (pinfunction "14_14") (pintype "passive"))
      (node (ref "LCD1") (pin "2") (pinfunction "2_2") (pintype "passive"))
      (node (ref "P4") (pin "1") (pinfunction "1_1") (pintype "passive"))
      (node (ref "P4") (pin "2") (pinfunction "2_2") (pintype "passive"))
      (node (ref "P5") (pin "1") (pinfunction "1_1") (pintype "passive"))
      (node (ref "P6") (pin "1") (pinfunction "1_1") (pintype "passive"))
      (node (ref "P7") (pin "1") (pinfunction "1_1") (pintype "passive"))
      (node (ref "POWER1") (pin "2") (pinfunction "2_2") (pintype "passive"))
      (node (ref "R27") (pin "2") (pinfunction "2_2") (pintype "passive"))
      (node (ref "R32") (pin "1") (pinfunction "1_1") (pintype "passive"))
      (node (ref "R33") (pin "1") (pinfunction "1_1") (pintype "passive"))
      (node (ref "R34") (pin "1") (pinfunction "1_1") (pintype "passive"))
      (node (ref "R35") (pin "1") (pinfunction "1_1") (pintype "passive"))
      (node (ref "R43") (pin "2") (pinfunction "2_2") (pintype "passive"))
      (node (ref "R44") (pin "2") (pinfunction "2_2") (pintype "passive"))
      (node (ref "R48") (pin "1") (pinfunction "1_1") (pintype "passive"))
      (node (ref "R49") (pin "1") (pinfunction "1_1") (pintype "passive"))
      (node (ref "R50") (pin "1") (pinfunction "1_1") (pintype "passive"))
      (node (ref "R56") (pin "1") (pinfunction "1_1") (pintype "passive"))
      (node (ref "R57") (pin "1") (pinfunction "1_1") (pintype "passive"))
      (node (ref "U10") (pin "1") (pinfunction "A0_1") (pintype "passive"))
      (node (ref "U10") (pin "2") (pinfunction "A1_2") (pintype "passive"))
      (node (ref "U10") (pin "3") (pinfunction "A2_3") (pintype "passive"))
      (node (ref "U10") (pin "4") (pinfunction "VSS_4") (pintype "passive"))
      (node (ref "U10") (pin "7") (pinfunction "WP_7") (pintype "passive"))
      (node (ref "U4") (pin "10") (pinfunction "VSS_5_10") (pintype "passive"))
      (node (ref "U4") (pin "19") (pinfunction "VSSA_19") (pintype "passive"))
      (node (ref "U4") (pin "20") (pinfunction "VREF-_20") (pintype "passive"))
      (node (ref "U4") (pin "27") (pinfunction "VSS_4_27") (pintype "passive"))
      (node (ref "U4") (pin "49") (pinfunction "VSS_1_49") (pintype "passive"))
      (node (ref "U4") (pin "74") (pinfunction "VSS_2_74") (pintype "passive"))
      (node (ref "U4") (pin "99") (pinfunction "VSS_3_99") (pintype "passive"))
      (node (ref "U5") (pin "2") (pinfunction "GND_2") (pintype "passive"))
      (node (ref "U6") (pin "2") (pinfunction "GND_2") (pintype "passive"))
      (node (ref "U7") (pin "1") (pinfunction "GND_1") (pintype "passive"))
      (node (ref "U8") (pin "15") (pinfunction "GND_15") (pintype "power_in"))
      (node (ref "U9") (pin "5") (pinfunction "GND_5") (pintype "passive"))
    )
    (net (code "61") (name "Net-(+1-+)") (class "Default")
      (node (ref "+1") (pin "1") (pinfunction "+_1") (pintype "passive"))
      (node (ref "R34") (pin "2") (pinfunction "2_2") (pintype "passive"))
    )
    (net (code "62") (name "Net-(+2-+)") (class "Default")
      (node (ref "+2") (pin "1") (pinfunction "+_1") (pintype "passive"))
      (node (ref "R35") (pin "2") (pinfunction "2_2") (pintype "passive"))
    )
    (net (code "63") (name "Net-(1-+)") (class "Default")
      (node (ref "1") (pin "1") (pinfunction "+_1") (pintype "passive"))
      (node (ref "R49") (pin "2") (pinfunction "2_2") (pintype "passive"))
    )
    (net (code "64") (name "Net-(2-+)") (class "Default")
      (node (ref "2") (pin "1") (pinfunction "+_1") (pintype "passive"))
      (node (ref "R50") (pin "2") (pinfunction "2_2") (pintype "passive"))
    )
    (net (code "65") (name "Net-(CANR1-+)") (class "Default")
      (node (ref "CANR1") (pin "1") (pinfunction "+_1") (pintype "passive"))
      (node (ref "R33") (pin "2") (pinfunction "2_2") (pintype "passive"))
    )
    (net (code "66") (name "Net-(CANT1-+)") (class "Default")
      (node (ref "CANT1") (pin "1") (pinfunction "+_1") (pintype "passive"))
      (node (ref "R32") (pin "2") (pinfunction "2_2") (pintype "passive"))
    )
    (net (code "67") (name "Net-(D12-K)") (class "Default")
      (node (ref "C15") (pin "2") (pinfunction "2_2") (pintype "passive"))
      (node (ref "D12") (pin "2") (pinfunction "K_2") (pintype "passive"))
      (node (ref "L1") (pin "1") (pinfunction "1_1") (pintype "passive"))
      (node (ref "U6") (pin "6") (pinfunction "SW_6") (pintype "passive"))
    )
    (net (code "68") (name "Net-(U4-OSC_IN)") (class "Default")
      (node (ref "C37") (pin "1") (pinfunction "1_1") (pintype "passive"))
      (node (ref "R45") (pin "1") (pinfunction "1_1") (pintype "passive"))
      (node (ref "U4") (pin "12") (pinfunction "OSC_IN_12") (pintype "passive"))
      (node (ref "Y2") (pin "1") (pinfunction "OSC1_1") (pintype "passive"))
    )
    (net (code "69") (name "Net-(U4-OSC_OUT)") (class "Default")
      (node (ref "C38") (pin "1") (pinfunction "1_1") (pintype "passive"))
      (node (ref "R45") (pin "2") (pinfunction "2_2") (pintype "passive"))
      (node (ref "U4") (pin "13") (pinfunction "OSC_OUT_13") (pintype "passive"))
      (node (ref "Y2") (pin "2") (pinfunction "OSC2_2") (pintype "passive"))
    )
    (net (code "70") (name "Net-(U4-PA4{slash}ADC123_IN4{slash}DAC_OUT1{slash}SPI1_NSS)") (class "Default")
      (node (ref "R28") (pin "1") (pinfunction "1_1") (pintype "passive"))
      (node (ref "U4") (pin "29") (pinfunction "PA4/ADC123_IN4/DAC_OUT1/SPI1_NSS_29") (pintype "passive"))
    )
    (net (code "71") (name "Net-(U4-PA5{slash}ADC123_IN5{slash}DAC_OUT2{slash}SPI1_SCK)") (class "Default")
      (node (ref "R31") (pin "1") (pinfunction "1_1") (pintype "passive"))
      (node (ref "U4") (pin "30") (pinfunction "PA5/ADC123_IN5/DAC_OUT2/SPI1_SCK_30") (pintype "passive"))
    )
    (net (code "72") (name "Net-(U4-PB0{slash}ADC123_IN8{slash}T3C3{slash}T8C2N{slash}T1C2N)") (class "Default")
      (node (ref "R36") (pin "1") (pinfunction "1_1") (pintype "passive"))
      (node (ref "U4") (pin "35") (pinfunction "PB0/ADC123_IN8/T3C3/T8C2N/T1C2N_35") (pintype "passive"))
    )
    (net (code "73") (name "Net-(U4-PC4{slash}ADC123_IN14)") (class "Default")
      (node (ref "R37") (pin "1") (pinfunction "1_1") (pintype "passive"))
      (node (ref "U4") (pin "33") (pinfunction "PC4/ADC123_IN14_33") (pintype "passive"))
    )
    (net (code "74") (name "Net-(U4-PC5{slash}ADC123_IN15)") (class "Default")
      (node (ref "R38") (pin "1") (pinfunction "1_1") (pintype "passive"))
      (node (ref "U4") (pin "34") (pinfunction "PC5/ADC123_IN15_34") (pintype "passive"))
    )
    (net (code "75") (name "Net-(U4-PC14-OSC32_IN)") (class "Default")
      (node (ref "C29") (pin "1") (pinfunction "1_1") (pintype "passive"))
      (node (ref "U4") (pin "8") (pinfunction "PC14-OSC32_IN_8") (pintype "passive"))
      (node (ref "Y1") (pin "2") (pinfunction "OSC2_2") (pintype "passive"))
    )
    (net (code "76") (name "Net-(U4-PC15-OSC32_OUT)") (class "Default")
      (node (ref "C28") (pin "1") (pinfunction "1_1") (pintype "passive"))
      (node (ref "U4") (pin "9") (pinfunction "PC15-OSC32_OUT_9") (pintype "passive"))
      (node (ref "Y1") (pin "1") (pinfunction "OSC1_1") (pintype "passive"))
    )
    (net (code "77") (name "Net-(U5-Rs)") (class "Default")
      (node (ref "R25") (pin "2") (pinfunction "2_2") (pintype "passive"))
      (node (ref "U5") (pin "8") (pinfunction "Rs_8") (pintype "passive"))
    )
    (net (code "78") (name "Net-(U6-BST)") (class "Default")
      (node (ref "C15") (pin "1") (pinfunction "1_1") (pintype "passive"))
      (node (ref "U6") (pin "1") (pinfunction "BST_1") (pintype "passive"))
    )
    (net (code "79") (name "Net-(U6-EN)") (class "Default")
      (node (ref "R29") (pin "2") (pinfunction "2_2") (pintype "passive"))
      (node (ref "U6") (pin "4") (pinfunction "EN_4") (pintype "passive"))
    )
    (net (code "80") (name "Net-(U6-FB)") (class "Default")
      (node (ref "R27") (pin "1") (pinfunction "1_1") (pintype "passive"))
      (node (ref "R30") (pin "1") (pinfunction "1_1") (pintype "passive"))
      (node (ref "U6") (pin "3") (pinfunction "FB_3") (pintype "passive"))
    )
    (net (code "81") (name "Net-(U8-C1+)") (class "Default")
      (node (ref "C25") (pin "1") (pinfunction "1_1") (pintype "passive"))
      (node (ref "U8") (pin "1") (pinfunction "C1+_1") (pintype "passive"))
    )
    (net (code "82") (name "Net-(U8-C1-)") (class "Default")
      (node (ref "C25") (pin "2") (pinfunction "2_2") (pintype "passive"))
      (node (ref "U8") (pin "3") (pinfunction "C1-_3") (pintype "passive"))
    )
    (net (code "83") (name "Net-(U8-C2+)") (class "Default")
      (node (ref "C27") (pin "1") (pinfunction "1_1") (pintype "passive"))
      (node (ref "U8") (pin "4") (pinfunction "C2+_4") (pintype "passive"))
    )
    (net (code "84") (name "Net-(U8-C2-)") (class "Default")
      (node (ref "C27") (pin "2") (pinfunction "2_2") (pintype "passive"))
      (node (ref "U8") (pin "5") (pinfunction "C2-_5") (pintype "passive"))
    )
    (net (code "85") (name "Net-(U8-R1IN)") (class "Default")
      (node (ref "J3") (pin "3") (pinfunction "3_3") (pintype "passive"))
      (node (ref "U8") (pin "13") (pinfunction "R1IN_13") (pintype "input"))
      (node (ref "Z2") (pin "2") (pintype "passive"))
    )
    (net (code "86") (name "Net-(U8-T1OUT)") (class "Default")
      (node (ref "J3") (pin "2") (pinfunction "2_2") (pintype "passive"))
      (node (ref "U8") (pin "14") (pinfunction "T1OUT_14") (pintype "output"))
      (node (ref "Z2") (pin "1") (pintype "passive"))
    )
    (net (code "87") (name "Net-(U8-VDD)") (class "Default")
      (node (ref "C26") (pin "2") (pinfunction "2_2") (pintype "passive"))
      (node (ref "U8") (pin "2") (pinfunction "VDD_2") (pintype "power_in"))
    )
    (net (code "88") (name "Net-(U8-VEE)") (class "Default")
      (node (ref "C30") (pin "2") (pinfunction "2_2") (pintype "passive"))
      (node (ref "U8") (pin "6") (pinfunction "VEE_6") (pintype "power_in"))
    )
    (net (code "89") (name "PE") (class "Default")
      (node (ref "CNT3") (pin "2") (pinfunction "2_2") (pintype "passive"))
      (node (ref "CNT3") (pin "5") (pinfunction "5_5") (pintype "passive"))
      (node (ref "D14") (pin "2") (pinfunction "K_2") (pintype "passive"))
      (node (ref "D15") (pin "2") (pinfunction "K_2") (pintype "passive"))
      (node (ref "Z1") (pin "3") (pintype "passive"))
      (node (ref "Z2") (pin "3") (pintype "passive"))
    )
    (net (code "90") (name "VCC3.3") (class "Default")
      (node (ref "+2") (pin "2") (pinfunction "-_2") (pintype "passive"))
      (node (ref "C20") (pin "2") (pinfunction "2_2") (pintype "passive"))
      (node (ref "C21") (pin "1") (pinfunction "1_1") (pintype "passive"))
      (node (ref "C23") (pin "1") (pinfunction "1_1") (pintype "passive"))
      (node (ref "C24") (pin "2") (pinfunction "2_2") (pintype "passive"))
      (node (ref "C31") (pin "2") (pinfunction "2_2") (pintype "passive"))
      (node (ref "C40") (pin "2") (pinfunction "2_2") (pintype "passive"))
      (node (ref "C41") (pin "2") (pinfunction "2_2") (pintype "passive"))
      (node (ref "C42") (pin "1") (pinfunction "1_1") (pintype "passive"))
      (node (ref "C43") (pin "1") (pinfunction "1_1") (pintype "passive"))
      (node (ref "C44") (pin "2") (pinfunction "2_2") (pintype "passive"))
      (node (ref "C45") (pin "2") (pinfunction "2_2") (pintype "passive"))
      (node (ref "C46") (pin "2") (pinfunction "2_2") (pintype "passive"))
      (node (ref "C47") (pin "2") (pinfunction "2_2") (pintype "passive"))
      (node (ref "C48") (pin "2") (pinfunction "2_2") (pintype "passive"))
      (node (ref "J4") (pin "4") (pinfunction "VDD_4") (pintype "passive"))
      (node (ref "JTAG1") (pin "1") (pinfunction "1_1") (pintype "passive"))
      (node (ref "LCD1") (pin "1") (pinfunction "1_1") (pintype "passive"))
      (node (ref "P4") (pin "10") (pinfunction "10_10") (pintype "passive"))
      (node (ref "R39") (pin "2") (pinfunction "2_2") (pintype "passive"))
      (node (ref "R40") (pin "2") (pinfunction "2_2") (pintype "passive"))
      (node (ref "R41") (pin "2") (pinfunction "2_2") (pintype "passive"))
      (node (ref "R42") (pin "2") (pinfunction "2_2") (pintype "passive"))
      (node (ref "R46") (pin "2") (pinfunction "2_2") (pintype "passive"))
      (node (ref "R51") (pin "1") (pinfunction "1_1") (pintype "passive"))
      (node (ref "R52") (pin "1") (pinfunction "1_1") (pintype "passive"))
      (node (ref "R53") (pin "1") (pinfunction "1_1") (pintype "passive"))
      (node (ref "R54") (pin "1") (pinfunction "1_1") (pintype "passive"))
      (node (ref "R55") (pin "1") (pinfunction "1_1") (pintype "passive"))
      (node (ref "U10") (pin "8") (pinfunction "VCC_8") (pintype "passive"))
      (node (ref "U4") (pin "100") (pinfunction "VDD_3_100") (pintype "passive"))
      (node (ref "U4") (pin "11") (pinfunction "VDD_5_11") (pintype "passive"))
      (node (ref "U4") (pin "21") (pinfunction "VREF+_21") (pintype "passive"))
      (node (ref "U4") (pin "22") (pinfunction "VDDA_22") (pintype "passive"))
      (node (ref "U4") (pin "28") (pinfunction "VDD_4_28") (pintype "passive"))
      (node (ref "U4") (pin "50") (pinfunction "VDD_1_50") (pintype "passive"))
      (node (ref "U4") (pin "75") (pinfunction "VDD_2_75") (pintype "passive"))
      (node (ref "U5") (pin "3") (pinfunction "VCC_3") (pintype "passive"))
      (node (ref "U7") (pin "2") (pinfunction "OUT_2") (pintype "passive"))
      (node (ref "U7") (pin "4") (pinfunction "OUT_4") (pintype "passive"))
      (node (ref "U8") (pin "16") (pinfunction "VCC_16") (pintype "power_in"))
      (node (ref "U9") (pin "8") (pinfunction "VCC_8") (pintype "passive"))
    )
    (net (code "91") (name "unconnected-(J3-MH1-Pad10)") (class "Default")
      (node (ref "J3") (pin "10") (pinfunction "MH1_10") (pintype "passive"))
    )
    (net (code "92") (name "unconnected-(J3-MH2-Pad11)") (class "Default")
      (node (ref "J3") (pin "11") (pinfunction "MH2_11") (pintype "passive"))
    )
    (net (code "93") (name "unconnected-(J3-Pad1)") (class "Default")
      (node (ref "J3") (pin "1") (pinfunction "1_1") (pintype "passive"))
    )
    (net (code "94") (name "unconnected-(J3-Pad4)") (class "Default")
      (node (ref "J3") (pin "4") (pinfunction "4_4") (pintype "passive"))
    )
    (net (code "95") (name "unconnected-(J3-Pad6)") (class "Default")
      (node (ref "J3") (pin "6") (pinfunction "6_6") (pintype "passive"))
    )
    (net (code "96") (name "unconnected-(J3-Pad7)") (class "Default")
      (node (ref "J3") (pin "7") (pinfunction "7_7") (pintype "passive"))
    )
    (net (code "97") (name "unconnected-(J3-Pad8)") (class "Default")
      (node (ref "J3") (pin "8") (pinfunction "8_8") (pintype "passive"))
    )
    (net (code "98") (name "unconnected-(J3-Pad9)") (class "Default")
      (node (ref "J3") (pin "9") (pinfunction "9_9") (pintype "passive"))
    )
    (net (code "99") (name "unconnected-(J4-Cd-Pad9)") (class "Default")
      (node (ref "J4") (pin "9") (pinfunction "Cd_9") (pintype "passive"))
    )
    (net (code "100") (name "unconnected-(P4-Pad3)") (class "Default")
      (node (ref "P4") (pin "3") (pinfunction "3_3") (pintype "passive"))
    )
    (net (code "101") (name "unconnected-(P4-Pad4)") (class "Default")
      (node (ref "P4") (pin "4") (pinfunction "4_4") (pintype "passive"))
    )
    (net (code "102") (name "unconnected-(P4-Pad11)") (class "Default")
      (node (ref "P4") (pin "11") (pinfunction "11_11") (pintype "passive"))
    )
    (net (code "103") (name "unconnected-(P4-Pad12)") (class "Default")
      (node (ref "P4") (pin "12") (pinfunction "12_12") (pintype "passive"))
    )
    (net (code "104") (name "unconnected-(U4-NC-Pad73)") (class "Default")
      (node (ref "U4") (pin "73") (pinfunction "NC_73") (pintype "passive"))
    )
    (net (code "105") (name "unconnected-(U4-PA0{slash}WKUP{slash}ADC123_IN0{slash}T2C1ETR{slash}T5C1{slash}T8ETR-Pad23)") (class "Default")
      (node (ref "U4") (pin "23") (pinfunction "PA0/WKUP/ADC123_IN0/T2C1ETR/T5C1/T8ETR_23") (pintype "passive"))
    )
    (net (code "106") (name "unconnected-(U4-PA1{slash}ADC123_IN1{slash}T5C2{slash}T2C2-Pad24)") (class "Default")
      (node (ref "U4") (pin "24") (pinfunction "PA1/ADC123_IN1/T5C2/T2C2_24") (pintype "passive"))
    )
    (net (code "107") (name "unconnected-(U4-PA8{slash}T1C1{slash}MCO-Pad67)") (class "Default")
      (node (ref "U4") (pin "67") (pinfunction "PA8/T1C1/MCO_67") (pintype "passive"))
    )
    (net (code "108") (name "unconnected-(U4-PA11{slash}CAN_Rx{slash}T1C4{slash}USBDM-Pad70)") (class "Default")
      (node (ref "U4") (pin "70") (pinfunction "PA11/CAN_Rx/T1C4/USBDM_70") (pintype "passive"))
    )
    (net (code "109") (name "unconnected-(U4-PA12{slash}CAN_Tx{slash}T1ETR{slash}USBDP-Pad71)") (class "Default")
      (node (ref "U4") (pin "71") (pinfunction "PA12/CAN_Tx/T1ETR/USBDP_71") (pintype "passive"))
    )
    (net (code "110") (name "unconnected-(U4-PB5{slash}I2C1_SMBA{slash}I2S3_SD{slash}SPI3_MOSI{slash}T3C2{slash}SPI1_MOSI-Pad91)") (class "Default")
      (node (ref "U4") (pin "91") (pinfunction "PB5/I2C1_SMBA/I2S3_SD/SPI3_MOSI/T3C2/SPI1_MOSI_91") (pintype "passive"))
    )
    (net (code "111") (name "unconnected-(U4-PB12{slash}I2S2_WS{slash}T1BKIN{slash}SPI2_NSS{slash}I2C2_SMBA-Pad51)") (class "Default")
      (node (ref "U4") (pin "51") (pinfunction "PB12/I2S2_WS/T1BKIN/SPI2_NSS/I2C2_SMBA_51") (pintype "passive"))
    )
    (net (code "112") (name "unconnected-(U4-PB13{slash}I2S2_CK{slash}T1CH1N{slash}SPI2_SCK-Pad52)") (class "Default")
      (node (ref "U4") (pin "52") (pinfunction "PB13/I2S2_CK/T1CH1N/SPI2_SCK_52") (pintype "passive"))
    )
    (net (code "113") (name "unconnected-(U4-PB14{slash}T1CH2N{slash}SPI2_MISO-Pad53)") (class "Default")
      (node (ref "U4") (pin "53") (pinfunction "PB14/T1CH2N/SPI2_MISO_53") (pintype "passive"))
    )
    (net (code "114") (name "unconnected-(U4-PB15{slash}I2S2_SD{slash}T1CH3N{slash}SPI2_MOSI-Pad54)") (class "Default")
      (node (ref "U4") (pin "54") (pinfunction "PB15/I2S2_SD/T1CH3N/SPI2_MOSI_54") (pintype "passive"))
    )
    (net (code "115") (name "unconnected-(U4-PC2{slash}ADC123_IN12-Pad17)") (class "Default")
      (node (ref "U4") (pin "17") (pinfunction "PC2/ADC123_IN12_17") (pintype "passive"))
    )
    (net (code "116") (name "unconnected-(U4-PC3{slash}ADC123_IN13-Pad18)") (class "Default")
      (node (ref "U4") (pin "18") (pinfunction "PC3/ADC123_IN13_18") (pintype "passive"))
    )
    (net (code "117") (name "unconnected-(U4-PC6{slash}I2S2_MCK{slash}T8C1{slash}T3C1{slash}SDIO_D6-Pad63)") (class "Default")
      (node (ref "U4") (pin "63") (pinfunction "PC6/I2S2_MCK/T8C1/T3C1/SDIO_D6_63") (pintype "passive"))
    )
    (net (code "118") (name "unconnected-(U4-PC7{slash}I2S3_MCK{slash}T8C2{slash}T3C2{slash}SDIO_D7-Pad64)") (class "Default")
      (node (ref "U4") (pin "64") (pinfunction "PC7/I2S3_MCK/T8C2/T3C2/SDIO_D7_64") (pintype "passive"))
    )
    (net (code "119") (name "unconnected-(U4-PC13-TAMPER-RTC-Pad7)") (class "Default")
      (node (ref "U4") (pin "7") (pinfunction "PC13-TAMPER-RTC_7") (pintype "passive"))
    )
    (net (code "120") (name "unconnected-(U4-PD3{slash}FSMC_CLK-Pad84)") (class "Default")
      (node (ref "U4") (pin "84") (pinfunction "PD3/FSMC_CLK_84") (pintype "passive"))
    )
    (net (code "121") (name "unconnected-(U4-PD4{slash}FSMC_NOE-Pad85)") (class "Default")
      (node (ref "U4") (pin "85") (pinfunction "PD4/FSMC_NOE_85") (pintype "passive"))
    )
    (net (code "122") (name "unconnected-(U4-PD7{slash}FSMC_NE1{slash}FSMC_NCE2-Pad88)") (class "Default")
      (node (ref "U4") (pin "88") (pinfunction "PD7/FSMC_NE1/FSMC_NCE2_88") (pintype "passive"))
    )
    (net (code "123") (name "unconnected-(U4-PD10{slash}FSMC_D15-Pad57)") (class "Default")
      (node (ref "U4") (pin "57") (pinfunction "PD10/FSMC_D15_57") (pintype "passive"))
    )
    (net (code "124") (name "unconnected-(U4-PD11{slash}FSMC_A16-Pad58)") (class "Default")
      (node (ref "U4") (pin "58") (pinfunction "PD11/FSMC_A16_58") (pintype "passive"))
    )
    (net (code "125") (name "unconnected-(U4-PD12{slash}T4C1{slash}FSMC_A17-Pad59)") (class "Default")
      (node (ref "U4") (pin "59") (pinfunction "PD12/T4C1/FSMC_A17_59") (pintype "passive"))
    )
    (net (code "126") (name "unconnected-(U4-PD13{slash}T4C2{slash}FSMC_A18-Pad60)") (class "Default")
      (node (ref "U4") (pin "60") (pinfunction "PD13/T4C2/FSMC_A18_60") (pintype "passive"))
    )
    (net (code "127") (name "unconnected-(U4-PD14{slash}T4C3{slash}FSMC_D0-Pad61)") (class "Default")
      (node (ref "U4") (pin "61") (pinfunction "PD14/T4C3/FSMC_D0_61") (pintype "passive"))
    )
    (net (code "128") (name "unconnected-(U4-PD15{slash}T4C4{slash}FSMC_D1-Pad62)") (class "Default")
      (node (ref "U4") (pin "62") (pinfunction "PD15/T4C4/FSMC_D1_62") (pintype "passive"))
    )
    (net (code "129") (name "unconnected-(U4-PE2{slash}TRACECK{slash}RSMC_A23-Pad1)") (class "Default")
      (node (ref "U4") (pin "1") (pinfunction "PE2/TRACECK/RSMC_A23_1") (pintype "passive"))
    )
    (net (code "130") (name "unconnected-(U4-PE3{slash}TRACED0{slash}FSMC_A19-Pad2)") (class "Default")
      (node (ref "U4") (pin "2") (pinfunction "PE3/TRACED0/FSMC_A19_2") (pintype "passive"))
    )
    (net (code "131") (name "unconnected-(U4-PE4{slash}TRACED1{slash}FSMC_A20-Pad3)") (class "Default")
      (node (ref "U4") (pin "3") (pinfunction "PE4/TRACED1/FSMC_A20_3") (pintype "passive"))
    )
    (net (code "132") (name "unconnected-(U4-PE5{slash}TRACED2{slash}FSMC_A21-Pad4)") (class "Default")
      (node (ref "U4") (pin "4") (pinfunction "PE5/TRACED2/FSMC_A21_4") (pintype "passive"))
    )
    (net (code "133") (name "unconnected-(U4-PE6{slash}TRACED3{slash}FSMC_A22-Pad5)") (class "Default")
      (node (ref "U4") (pin "5") (pinfunction "PE6/TRACED3/FSMC_A22_5") (pintype "passive"))
    )
    (net (code "134") (name "unconnected-(U4-PE10{slash}FSMC_D7{slash}T1CH2N-Pad41)") (class "Default")
      (node (ref "U4") (pin "41") (pinfunction "PE10/FSMC_D7/T1CH2N_41") (pintype "passive"))
    )
    (net (code "135") (name "unconnected-(U4-PE11{slash}FSMC_D8{slash}T1C2-Pad42)") (class "Default")
      (node (ref "U4") (pin "42") (pinfunction "PE11/FSMC_D8/T1C2_42") (pintype "passive"))
    )
    (net (code "136") (name "unconnected-(U4-PE12{slash}FSMC_D9{slash}T1CH3N-Pad43)") (class "Default")
      (node (ref "U4") (pin "43") (pinfunction "PE12/FSMC_D9/T1CH3N_43") (pintype "passive"))
    )
    (net (code "137") (name "unconnected-(U4-PE13{slash}FSMC_D10{slash}T1C3-Pad44)") (class "Default")
      (node (ref "U4") (pin "44") (pinfunction "PE13/FSMC_D10/T1C3_44") (pintype "passive"))
    )
    (net (code "138") (name "unconnected-(U4-PE14{slash}FSMC_D11{slash}T1C4-Pad45)") (class "Default")
      (node (ref "U4") (pin "45") (pinfunction "PE14/FSMC_D11/T1C4_45") (pintype "passive"))
    )
    (net (code "139") (name "unconnected-(U4-PE15{slash}FSMC_D12{slash}T1BKIN-Pad46)") (class "Default")
      (node (ref "U4") (pin "46") (pinfunction "PE15/FSMC_D12/T1BKIN_46") (pintype "passive"))
    )
    (net (code "140") (name "unconnected-(U5-Vref-Pad5)") (class "Default")
      (node (ref "U5") (pin "5") (pinfunction "Vref_5") (pintype "passive"))
    )
    (net (code "141") (name "unconnected-(U8-R2IN-Pad8)") (class "Default")
      (node (ref "U8") (pin "8") (pinfunction "R2IN_8") (pintype "input"))
    )
    (net (code "142") (name "unconnected-(U8-R2OUT-Pad9)") (class "Default")
      (node (ref "U8") (pin "9") (pinfunction "R2OUT_9") (pintype "output"))
    )
    (net (code "143") (name "unconnected-(U8-T2IN-Pad10)") (class "Default")
      (node (ref "U8") (pin "10") (pinfunction "T2IN_10") (pintype "input"))
    )
    (net (code "144") (name "unconnected-(U8-T2OUT-Pad7)") (class "Default")
      (node (ref "U8") (pin "7") (pinfunction "T2OUT_7") (pintype "output"))
    )
    (net (code "145") (name "unconnected-(Y1-Pad3)") (class "Default")
      (node (ref "Y1") (pin "3") (pinfunction "3_3") (pintype "passive"))
    )
    (net (code "146") (name "unconnected-(Y2-Pad3)") (class "Default")
      (node (ref "Y2") (pin "3") (pinfunction "3_3") (pintype "passive"))
    )
  )
)
